# xvz13tf-EU.net
KiCad netlist of a schematic drawn in EAGLE
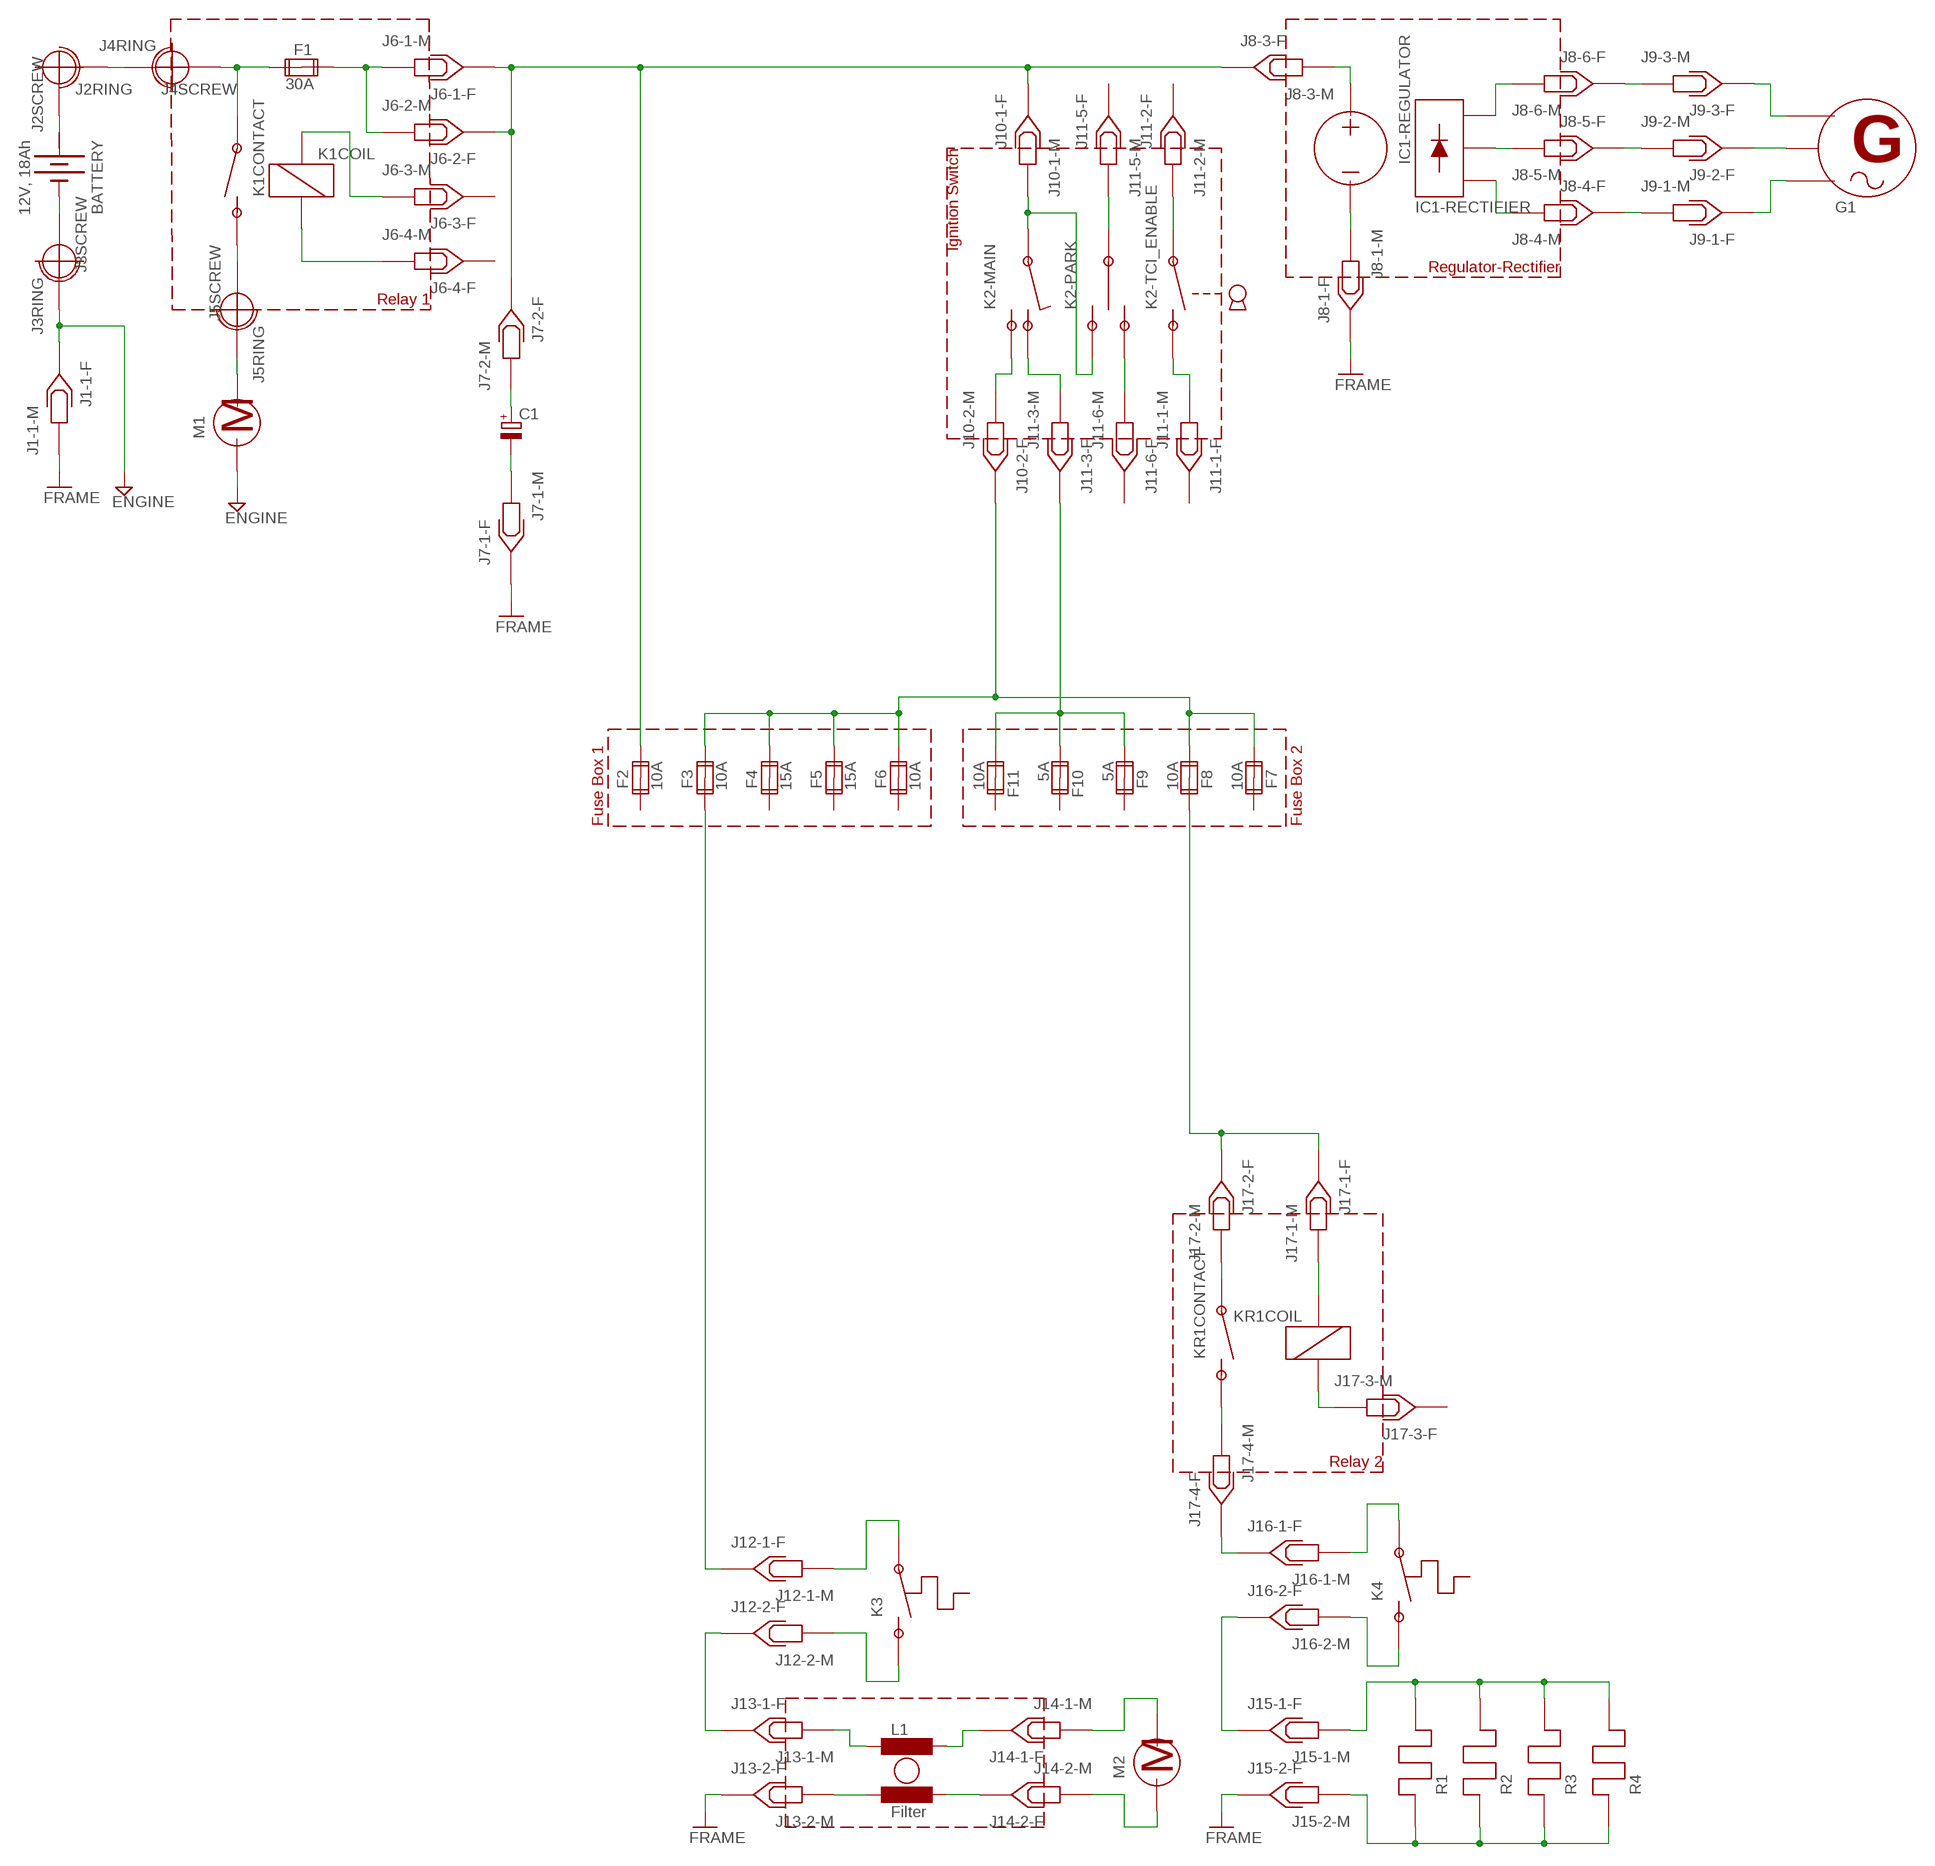
[diagram p0: schematic, sheet 1]

(export (version "E")
  (design (tool "Eeschema 10.0.6"))
  (components
    (comp (ref "BATTERY")
      (value "12V, 18Ah")
      (footprint "eagle-import:BATTERY")
      (libsource (lib "eagle-import") (part "BATTERY"))
    )
    (comp (ref "C1")
      (value "CPOL-EUE10-35")
      (footprint "eagle-import:EB35D")
      (libsource (lib "eagle-import") (part "CPOL-EUE10-35"))
    )
    (comp (ref "F1")
      (value "30A")
      (footprint "eagle-import:FUSE1")
      (libsource (lib "eagle-import") (part "FUSE2P"))
    )
    (comp (ref "F2")
      (value "10A")
      (footprint "eagle-import:FUSE1")
      (libsource (lib "eagle-import") (part "FUSE2P"))
    )
    (comp (ref "F3")
      (value "10A")
      (footprint "eagle-import:FUSE1")
      (libsource (lib "eagle-import") (part "FUSE2P"))
    )
    (comp (ref "F4")
      (value "15A")
      (footprint "eagle-import:FUSE1")
      (libsource (lib "eagle-import") (part "FUSE2P"))
    )
    (comp (ref "F5")
      (value "15A")
      (footprint "eagle-import:FUSE1")
      (libsource (lib "eagle-import") (part "FUSE2P"))
    )
    (comp (ref "F6")
      (value "10A")
      (footprint "eagle-import:FUSE1")
      (libsource (lib "eagle-import") (part "FUSE2P"))
    )
    (comp (ref "F7")
      (value "10A")
      (footprint "eagle-import:FUSE1")
      (libsource (lib "eagle-import") (part "FUSE2P"))
    )
    (comp (ref "F8")
      (value "10A")
      (footprint "eagle-import:FUSE1")
      (libsource (lib "eagle-import") (part "FUSE2P"))
    )
    (comp (ref "F9")
      (value "5A")
      (footprint "eagle-import:FUSE1")
      (libsource (lib "eagle-import") (part "FUSE2P"))
    )
    (comp (ref "F10")
      (value "5A")
      (footprint "eagle-import:FUSE1")
      (libsource (lib "eagle-import") (part "FUSE2P"))
    )
    (comp (ref "F11")
      (value "10A")
      (footprint "eagle-import:FUSE1")
      (libsource (lib "eagle-import") (part "FUSE2P"))
    )
    (comp (ref "L1")
      (value "Filter")
      (footprint "eagle-import:R18")
      (libsource (lib "eagle-import") (part "R18"))
    )
  )
  (nets
    (net (code "1") (name "/+") (class "Default")
      (node (ref "BATTERY") (pin "+@1") (pinfunction "+_+@1") (pintype "power_in"))
    )
    (net (code "4") (name "ENGINE") (class "Default")
      (node (ref "BATTERY") (pin "+") (pinfunction "+_+") (pintype "power_in"))
      (node (ref "BATTERY") (pin "-") (pinfunction "-_-") (pintype "power_in"))
      (node (ref "C1") (pin "+") (pinfunction "+_+") (pintype "passive"))
      (node (ref "C1") (pin "-") (pinfunction "-_-") (pintype "passive"))
      (node (ref "F1") (pin "1A") (pinfunction "1A_1A") (pintype "passive"))
      (node (ref "F1") (pin "2A") (pinfunction "2A_2A") (pintype "passive"))
      (node (ref "F10") (pin "1A") (pinfunction "1A_1A") (pintype "passive"))
      (node (ref "F11") (pin "1A") (pinfunction "1A_1A") (pintype "passive"))
      (node (ref "F2") (pin "1A") (pinfunction "1A_1A") (pintype "passive"))
      (node (ref "F3") (pin "1A") (pinfunction "1A_1A") (pintype "passive"))
      (node (ref "F3") (pin "2A") (pinfunction "2A_2A") (pintype "passive"))
      (node (ref "F4") (pin "1A") (pinfunction "1A_1A") (pintype "passive"))
      (node (ref "F5") (pin "1A") (pinfunction "1A_1A") (pintype "passive"))
      (node (ref "F6") (pin "1A") (pinfunction "1A_1A") (pintype "passive"))
      (node (ref "F7") (pin "1A") (pinfunction "1A_1A") (pintype "passive"))
      (node (ref "F8") (pin "1A") (pinfunction "1A_1A") (pintype "passive"))
      (node (ref "F8") (pin "2A") (pinfunction "2A_2A") (pintype "passive"))
      (node (ref "F9") (pin "1A") (pinfunction "1A_1A") (pintype "passive"))
      (node (ref "L1") (pin "1") (pinfunction "1_1") (pintype "passive"))
      (node (ref "L1") (pin "2") (pinfunction "2_2") (pintype "passive"))
      (node (ref "L1") (pin "3") (pinfunction "3_3") (pintype "passive"))
      (node (ref "L1") (pin "4") (pinfunction "4_4") (pintype "passive"))
    )
    (net (code "5") (name "unconnected-(F1-Pad1B)") (class "Default")
      (node (ref "F1") (pin "1B") (pinfunction "1B_1B") (pintype "passive"))
    )
    (net (code "6") (name "unconnected-(F1-Pad2B)") (class "Default")
      (node (ref "F1") (pin "2B") (pinfunction "2B_2B") (pintype "passive"))
    )
    (net (code "7") (name "unconnected-(F2-Pad1B)") (class "Default")
      (node (ref "F2") (pin "1B") (pinfunction "1B_1B") (pintype "passive"))
    )
    (net (code "8") (name "unconnected-(F2-Pad2A)") (class "Default")
      (node (ref "F2") (pin "2A") (pinfunction "2A_2A") (pintype "passive"))
    )
    (net (code "9") (name "unconnected-(F2-Pad2B)") (class "Default")
      (node (ref "F2") (pin "2B") (pinfunction "2B_2B") (pintype "passive"))
    )
    (net (code "10") (name "unconnected-(F3-Pad1B)") (class "Default")
      (node (ref "F3") (pin "1B") (pinfunction "1B_1B") (pintype "passive"))
    )
    (net (code "11") (name "unconnected-(F3-Pad2B)") (class "Default")
      (node (ref "F3") (pin "2B") (pinfunction "2B_2B") (pintype "passive"))
    )
    (net (code "12") (name "unconnected-(F4-Pad1B)") (class "Default")
      (node (ref "F4") (pin "1B") (pinfunction "1B_1B") (pintype "passive"))
    )
    (net (code "13") (name "unconnected-(F4-Pad2A)") (class "Default")
      (node (ref "F4") (pin "2A") (pinfunction "2A_2A") (pintype "passive"))
    )
    (net (code "14") (name "unconnected-(F4-Pad2B)") (class "Default")
      (node (ref "F4") (pin "2B") (pinfunction "2B_2B") (pintype "passive"))
    )
    (net (code "15") (name "unconnected-(F5-Pad1B)") (class "Default")
      (node (ref "F5") (pin "1B") (pinfunction "1B_1B") (pintype "passive"))
    )
    (net (code "16") (name "unconnected-(F5-Pad2A)") (class "Default")
      (node (ref "F5") (pin "2A") (pinfunction "2A_2A") (pintype "passive"))
    )
    (net (code "17") (name "unconnected-(F5-Pad2B)") (class "Default")
      (node (ref "F5") (pin "2B") (pinfunction "2B_2B") (pintype "passive"))
    )
    (net (code "18") (name "unconnected-(F6-Pad1B)") (class "Default")
      (node (ref "F6") (pin "1B") (pinfunction "1B_1B") (pintype "passive"))
    )
    (net (code "19") (name "unconnected-(F6-Pad2A)") (class "Default")
      (node (ref "F6") (pin "2A") (pinfunction "2A_2A") (pintype "passive"))
    )
    (net (code "20") (name "unconnected-(F6-Pad2B)") (class "Default")
      (node (ref "F6") (pin "2B") (pinfunction "2B_2B") (pintype "passive"))
    )
    (net (code "21") (name "unconnected-(F7-Pad1B)") (class "Default")
      (node (ref "F7") (pin "1B") (pinfunction "1B_1B") (pintype "passive"))
    )
    (net (code "22") (name "unconnected-(F7-Pad2A)") (class "Default")
      (node (ref "F7") (pin "2A") (pinfunction "2A_2A") (pintype "passive"))
    )
    (net (code "23") (name "unconnected-(F7-Pad2B)") (class "Default")
      (node (ref "F7") (pin "2B") (pinfunction "2B_2B") (pintype "passive"))
    )
    (net (code "24") (name "unconnected-(F8-Pad1B)") (class "Default")
      (node (ref "F8") (pin "1B") (pinfunction "1B_1B") (pintype "passive"))
    )
    (net (code "25") (name "unconnected-(F8-Pad2B)") (class "Default")
      (node (ref "F8") (pin "2B") (pinfunction "2B_2B") (pintype "passive"))
    )
    (net (code "26") (name "unconnected-(F9-Pad1B)") (class "Default")
      (node (ref "F9") (pin "1B") (pinfunction "1B_1B") (pintype "passive"))
    )
    (net (code "27") (name "unconnected-(F9-Pad2A)") (class "Default")
      (node (ref "F9") (pin "2A") (pinfunction "2A_2A") (pintype "passive"))
    )
    (net (code "28") (name "unconnected-(F9-Pad2B)") (class "Default")
      (node (ref "F9") (pin "2B") (pinfunction "2B_2B") (pintype "passive"))
    )
    (net (code "29") (name "unconnected-(F10-Pad1B)") (class "Default")
      (node (ref "F10") (pin "1B") (pinfunction "1B_1B") (pintype "passive"))
    )
    (net (code "30") (name "unconnected-(F10-Pad2A)") (class "Default")
      (node (ref "F10") (pin "2A") (pinfunction "2A_2A") (pintype "passive"))
    )
    (net (code "31") (name "unconnected-(F10-Pad2B)") (class "Default")
      (node (ref "F10") (pin "2B") (pinfunction "2B_2B") (pintype "passive"))
    )
    (net (code "32") (name "unconnected-(F11-Pad1B)") (class "Default")
      (node (ref "F11") (pin "1B") (pinfunction "1B_1B") (pintype "passive"))
    )
    (net (code "33") (name "unconnected-(F11-Pad2A)") (class "Default")
      (node (ref "F11") (pin "2A") (pinfunction "2A_2A") (pintype "passive"))
    )
    (net (code "34") (name "unconnected-(F11-Pad2B)") (class "Default")
      (node (ref "F11") (pin "2B") (pinfunction "2B_2B") (pintype "passive"))
    )
  )
)
